# Amoled.net
KiCad netlist of a schematic drawn in Altium Designer
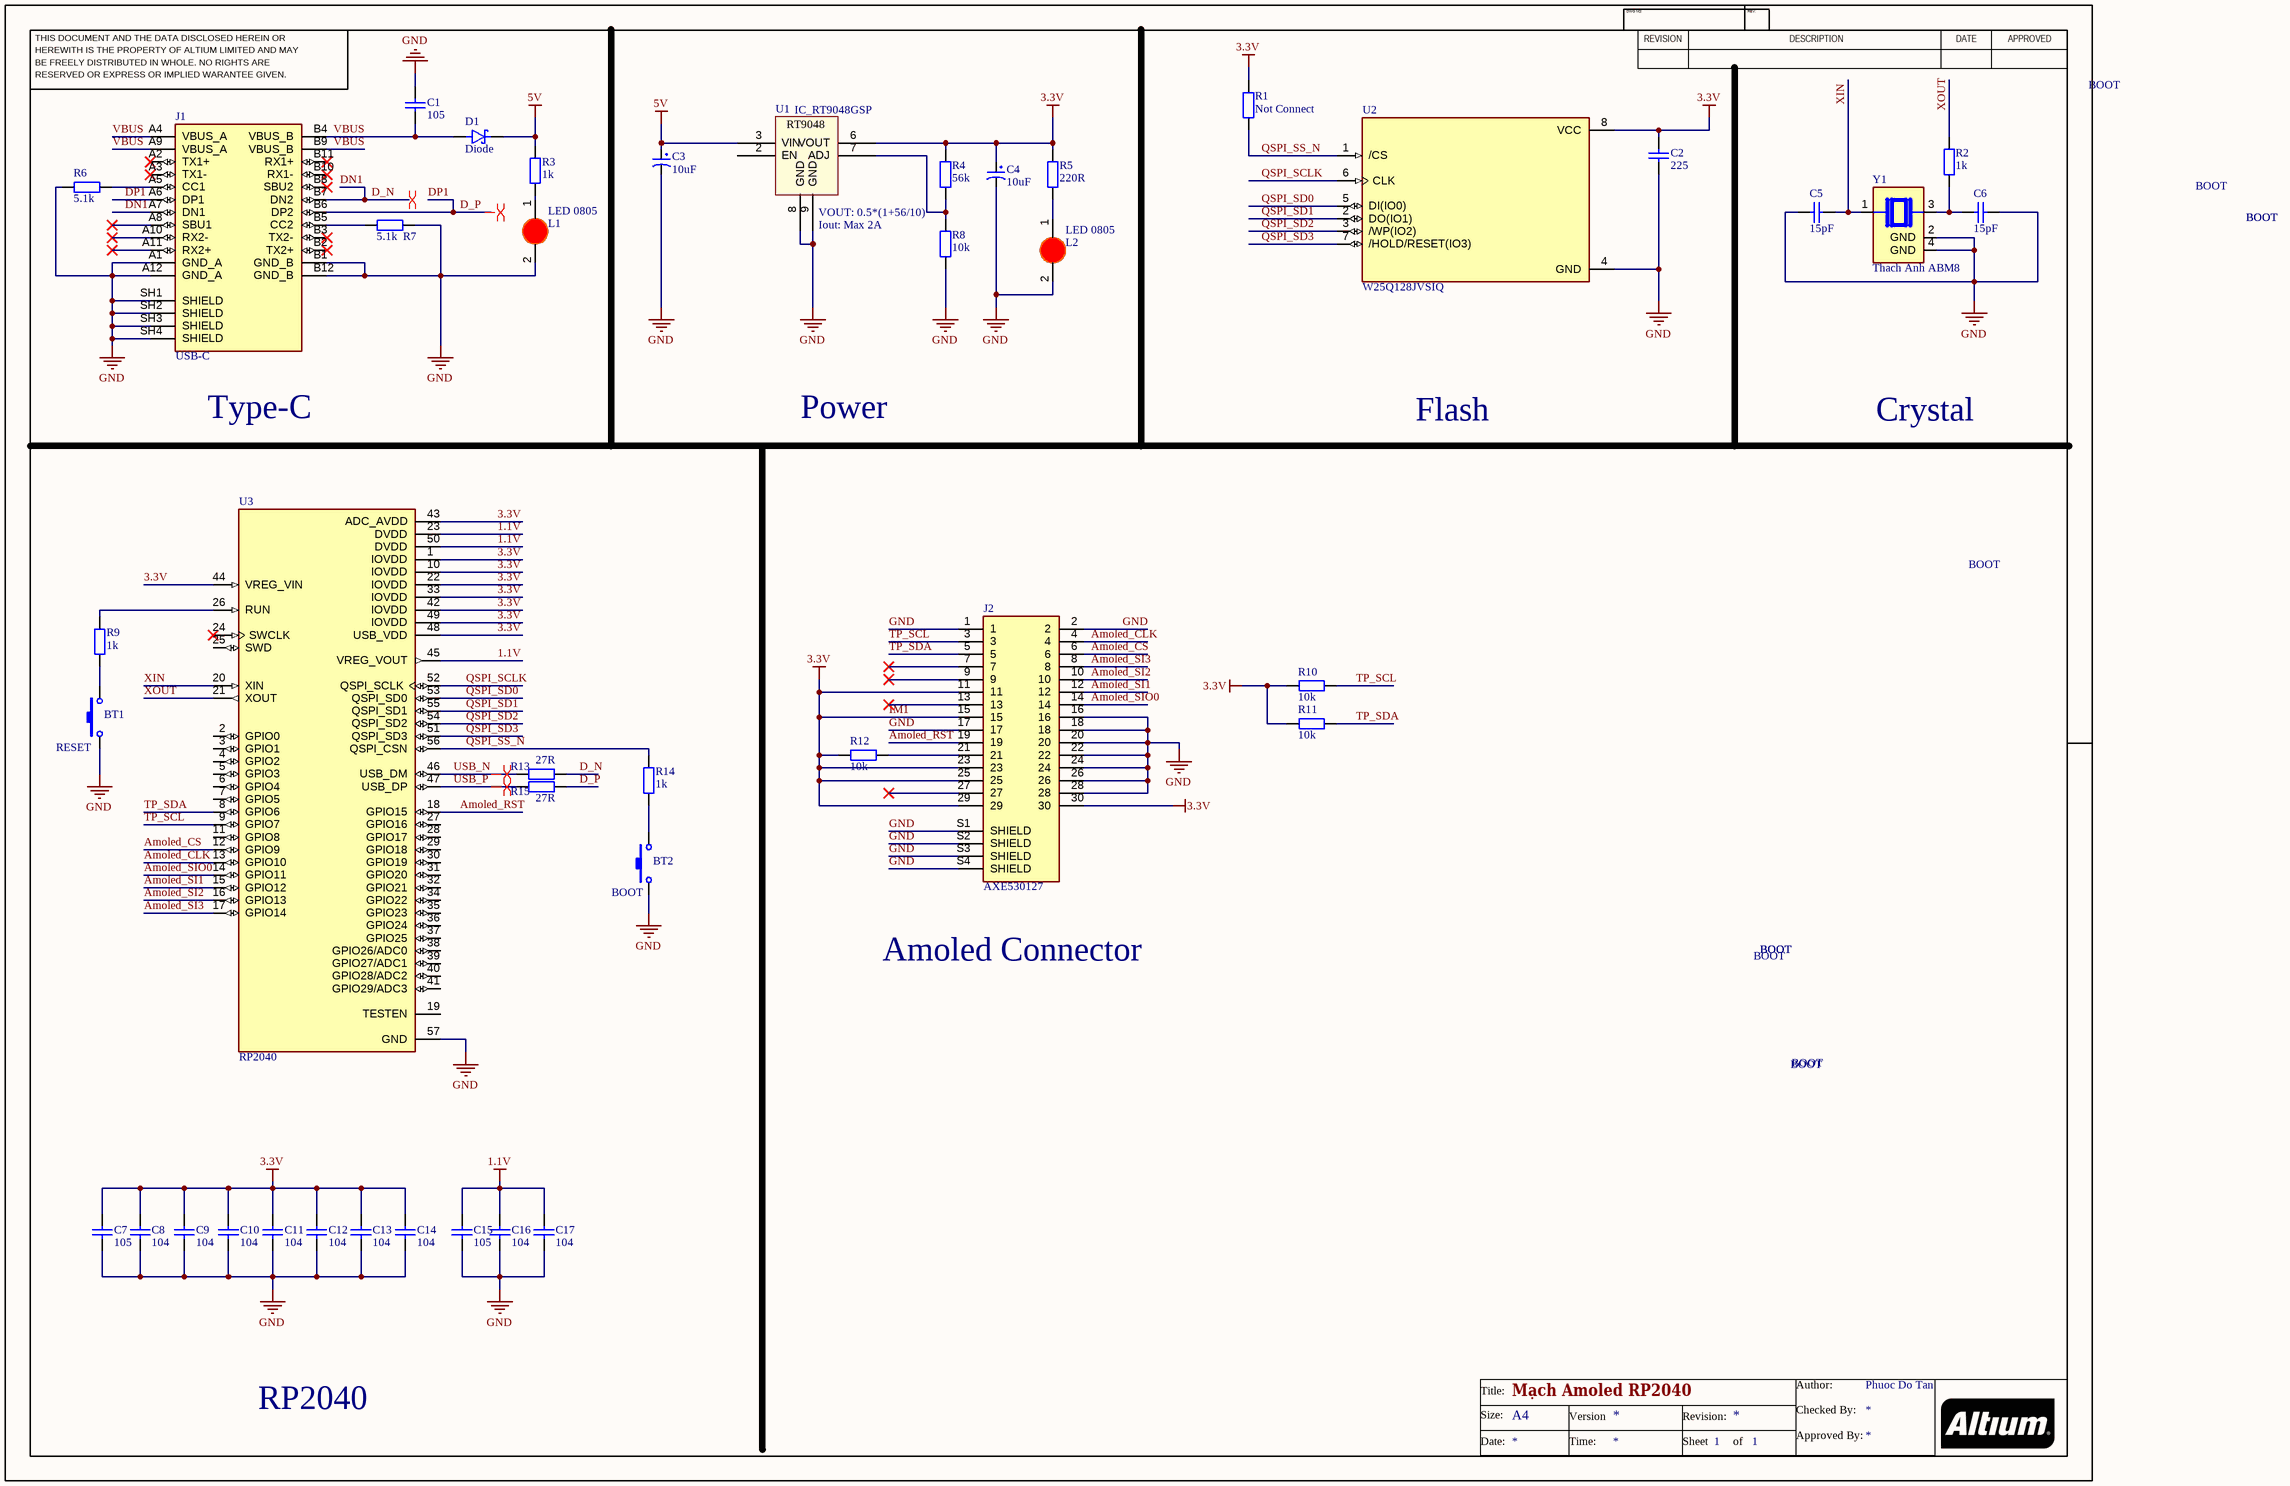
[diagram p0: Amoled.SchDoc]

(export (version "E")
  (design (tool "Eeschema 10.0.6"))
  (components
    (comp (ref "BT1")
      (value "Nut Nhan 2 Chan SMD 3x6x2.5")
      (footprint "Nut Nhan 2 Chan SMD 3x6x2.5")
      (libsource (lib "Altium_Lib_by_KhueNguyenCreator") (part "Nut Nhan 2 Chan SMD 3x6x2.5"))
    )
    (comp (ref "BT2")
      (value "Nut Nhan 2 Chan SMD 3x6x2.5")
      (footprint "Nut Nhan 2 Chan SMD 3x6x2.5")
      (libsource (lib "Altium_Lib_by_KhueNguyenCreator") (part "Nut Nhan 2 Chan SMD 3x6x2.5"))
    )
    (comp (ref "C1")
      (value "105")
      (footprint "tu 0805")
      (description "Dán")
      (libsource (lib "Altium_Lib_by_KhueNguyenCreator") (part "Tu 0805 105 50V 10%"))
    )
    (comp (ref "C2")
      (value "225")
      (footprint "tu 0805")
      (description "Dán")
      (libsource (lib "Altium_Lib_by_KhueNguyenCreator") (part "Tu 0805 225 25V 10%"))
    )
    (comp (ref "C3")
      (value "10uF")
      (footprint "tu tantalum smd3216")
      (description "Dán")
      (libsource (lib "Altium_Lib_by_KhueNguyenCreator") (part "Tu tantalum 10uF 16V SMD3216"))
    )
    (comp (ref "C4")
      (value "10uF")
      (footprint "tu tantalum smd3216")
      (description "Dán")
      (libsource (lib "Altium_Lib_by_KhueNguyenCreator") (part "Tu tantalum 10uF 16V SMD3216"))
    )
    (comp (ref "C5")
      (value "15pF")
      (footprint "tu 0805")
      (description "Dán")
      (libsource (lib "Altium_Lib_by_KhueNguyenCreator") (part "Tu 0805 15pF 50V 10%"))
    )
    (comp (ref "C6")
      (value "15pF")
      (footprint "tu 0805")
      (description "Dán")
      (libsource (lib "Altium_Lib_by_KhueNguyenCreator") (part "Tu 0805 15pF 50V 10%"))
    )
    (comp (ref "C7")
      (value "105")
      (footprint "tu 0805")
      (description "Dán")
      (libsource (lib "Altium_Lib_by_KhueNguyenCreator") (part "Tu 0805 105 50V 10%"))
    )
    (comp (ref "C8")
      (value "104")
      (footprint "tu 0805")
      (description "Dán")
      (libsource (lib "Altium_Lib_by_KhueNguyenCreator") (part "Tu 0805 104 50V 10%"))
    )
    (comp (ref "C9")
      (value "104")
      (footprint "tu 0805")
      (description "Dán")
      (libsource (lib "Altium_Lib_by_KhueNguyenCreator") (part "Tu 0805 104 50V 10%"))
    )
    (comp (ref "C10")
      (value "104")
      (footprint "tu 0805")
      (description "Dán")
      (libsource (lib "Altium_Lib_by_KhueNguyenCreator") (part "Tu 0805 104 50V 10%"))
    )
    (comp (ref "C11")
      (value "104")
      (footprint "tu 0805")
      (description "Dán")
      (libsource (lib "Altium_Lib_by_KhueNguyenCreator") (part "Tu 0805 104 50V 10%"))
    )
    (comp (ref "C12")
      (value "104")
      (footprint "tu 0805")
      (description "Dán")
      (libsource (lib "Altium_Lib_by_KhueNguyenCreator") (part "Tu 0805 104 50V 10%"))
    )
    (comp (ref "C13")
      (value "104")
      (footprint "tu 0805")
      (description "Dán")
      (libsource (lib "Altium_Lib_by_KhueNguyenCreator") (part "Tu 0805 104 50V 10%"))
    )
    (comp (ref "C14")
      (value "104")
      (footprint "tu 0805")
      (description "Dán")
      (libsource (lib "Altium_Lib_by_KhueNguyenCreator") (part "Tu 0805 104 50V 10%"))
    )
    (comp (ref "C15")
      (value "105")
      (footprint "tu 0805")
      (description "Dán")
      (libsource (lib "Altium_Lib_by_KhueNguyenCreator") (part "Tu 0805 105 50V 10%"))
    )
    (comp (ref "C16")
      (value "104")
      (footprint "tu 0805")
      (description "Dán")
      (libsource (lib "Altium_Lib_by_KhueNguyenCreator") (part "Tu 0805 104 50V 10%"))
    )
    (comp (ref "C17")
      (value "104")
      (footprint "tu 0805")
      (description "Dán")
      (libsource (lib "Altium_Lib_by_KhueNguyenCreator") (part "Tu 0805 104 50V 10%"))
    )
    (comp (ref "D1")
      (value "Diode")
      (footprint "SODFL3619X98N")
      (description "Diode Schottky 30 V 2A Surface Mount SOD-123FL")
      (fields (field (name "MF") "ON Semiconductor") (field (name "MP") "MBR230LSFT1G"))
      (libsource (lib "Altium_Lib_by_KhueNguyenCreator") (part "Diode-MBR230LSFT1G"))
    )
    (comp (ref "J1")
      (value "USB-C")
      (footprint "USB-C")
      (fields (field (name "MP") "2345986-1") (field (name "PART NUMBER") "TE2345986-1"))
      (libsource (lib "Altium_Lib_by_KhueNguyenCreator") (part "USB-C"))
    )
    (comp (ref "J2")
      (value "AXE530127")
      (footprint "PANASONIC_AXE530127")
      (description "30 Position Connector Socket, Center Strip Contacts Surface Mount Gold")
      (fields (field (name "MF") "Panasonic Electric Works"))
      (libsource (lib "Altium_Lib_by_KhueNguyenCreator") (part "AXE530127"))
    )
    (comp (ref "L1")
      (value "LED 0805")
      (footprint "LED-0805-Red")
      (description "Dán")
      (libsource (lib "Altium_Lib_by_KhueNguyenCreator") (part "LED 0805 Do"))
    )
    (comp (ref "L2")
      (value "LED 0805")
      (footprint "LED-0805-Red")
      (description "Dán")
      (libsource (lib "Altium_Lib_by_KhueNguyenCreator") (part "LED 0805 Do"))
    )
    (comp (ref "R1")
      (value "Not Connect")
      (footprint "tro smd 0805")
      (description "Dán")
      (libsource (lib "Altium_Lib_by_KhueNguyenCreator") (part "Tro 0805 5% 0R"))
    )
    (comp (ref "R2")
      (value "1k")
      (footprint "tro smd 0805")
      (description "Dán")
      (libsource (lib "Altium_Lib_by_KhueNguyenCreator") (part "Tro 0805 5% 1k"))
    )
    (comp (ref "R3")
      (value "1k")
      (footprint "tro smd 0805")
      (description "Dán")
      (libsource (lib "Altium_Lib_by_KhueNguyenCreator") (part "Tro 0805 5% 1k"))
    )
    (comp (ref "R4")
      (value "56k")
      (footprint "tro smd 0805")
      (description "Dán")
      (libsource (lib "Altium_Lib_by_KhueNguyenCreator") (part "Tro 0805 1% 510k"))
    )
    (comp (ref "R5")
      (value "220R")
      (footprint "tro smd 0805")
      (description "Dán")
      (libsource (lib "Altium_Lib_by_KhueNguyenCreator") (part "Tro 0805 5% 220R"))
    )
    (comp (ref "R6")
      (value "5.1k")
      (footprint "tro smd 0805")
      (description "Dán")
      (libsource (lib "Altium_Lib_by_KhueNguyenCreator") (part "Tro 0805 1% 5.1k"))
    )
    (comp (ref "R7")
      (value "5.1k")
      (footprint "tro smd 0805")
      (description "Dán")
      (libsource (lib "Altium_Lib_by_KhueNguyenCreator") (part "Tro 0805 1% 5.1k"))
    )
    (comp (ref "R8")
      (value "10k")
      (footprint "tro smd 0805")
      (description "Dán")
      (libsource (lib "Altium_Lib_by_KhueNguyenCreator") (part "Tro 0805 1% 10k"))
    )
    (comp (ref "R9")
      (value "1k")
      (footprint "tro smd 0805")
      (description "Dán")
      (libsource (lib "Altium_Lib_by_KhueNguyenCreator") (part "Tro 0805 5% 1k"))
    )
    (comp (ref "R10")
      (value "10k")
      (footprint "tro smd 0805")
      (description "Dán")
      (libsource (lib "Altium_Lib_by_KhueNguyenCreator") (part "Tro 0805 1% 10k"))
    )
    (comp (ref "R11")
      (value "10k")
      (footprint "tro smd 0805")
      (description "Dán")
      (libsource (lib "Altium_Lib_by_KhueNguyenCreator") (part "Tro 0805 1% 10k"))
    )
    (comp (ref "R12")
      (value "10k")
      (footprint "tro smd 0805")
      (description "Dán")
      (libsource (lib "Altium_Lib_by_KhueNguyenCreator") (part "Tro 0805 1% 10k"))
    )
    (comp (ref "R13")
      (value "27R")
      (footprint "tro smd 0805")
      (description "Dán")
      (libsource (lib "Altium_Lib_by_KhueNguyenCreator") (part "Tro 0805 1% 18k"))
    )
    (comp (ref "R14")
      (value "1k")
      (footprint "tro smd 0805")
      (description "Dán")
      (libsource (lib "Altium_Lib_by_KhueNguyenCreator") (part "Tro 0805 5% 1k"))
    )
    (comp (ref "R15")
      (value "27R")
      (footprint "tro smd 0805")
      (description "Dán")
      (libsource (lib "Altium_Lib_by_KhueNguyenCreator") (part "Tro 0805 1% 18k"))
    )
    (comp (ref "U1")
      (value "IC_RT9048GSP")
      (footprint "SOP-8(Exposed Pad)")
      (libsource (lib "Altium_Lib_by_KhueNguyenCreator") (part "IC_RT9048GSP"))
    )
    (comp (ref "U2")
      (value "W25Q128JVSIQ")
      (footprint "SOIC127P790X216-8N")
      (description "FLASH - NOR Memory IC 128Mb (16M x 8) SPI - Quad I/O, QPI, DTR 133 MHz 8-SOIC")
      (fields (field (name "MF") "Winbond Electronics"))
      (libsource (lib "Altium_Lib_by_KhueNguyenCreator") (part "W25Q128JVSIQ"))
    )
    (comp (ref "U3")
      (value "RP2040")
      (footprint "RP2040")
      (description "RP2040 chip for Raspberry Pi Pico - ARM® Cortex®-M0+ MCU 32-Bit")
      (fields (field (name "MF") "Raspberry Pi"))
      (libsource (lib "Altium_Lib_by_KhueNguyenCreator") (part "RP2040"))
    )
    (comp (ref "Y1")
      (value "Thach Anh ABM8")
      (footprint "XTAL_ABM8-272-T3")
      (description "12 MHz Â±30ppm Crystal 10pF 50 Ohms 4-SMD, No Lead")
      (fields (field (name "MF") "ABRACON") (field (name "MP") "ABM8-272-T3"))
      (libsource (lib "Altium_Lib_by_KhueNguyenCreator") (part "Thach Anh ABM8"))
    )
  )
  (nets
    (net (code "1") (name "/Amoled_CLK") (class "Default")
      (node (ref "J2") (pin "4") (pinfunction "4_4") (pintype "passive"))
      (node (ref "U3") (pin "13") (pinfunction "GPIO10_13") (pintype "bidirectional"))
    )
    (net (code "2") (name "/Amoled_CS") (class "Default")
      (node (ref "J2") (pin "6") (pinfunction "6_6") (pintype "passive"))
      (node (ref "U3") (pin "12") (pinfunction "GPIO9_12") (pintype "bidirectional"))
    )
    (net (code "3") (name "/Amoled_RST") (class "Default")
      (node (ref "J2") (pin "19") (pinfunction "19_19") (pintype "passive"))
      (node (ref "U3") (pin "18") (pinfunction "GPIO15_18") (pintype "bidirectional"))
    )
    (net (code "4") (name "/Amoled_SI1") (class "Default")
      (node (ref "J2") (pin "12") (pinfunction "12_12") (pintype "passive"))
      (node (ref "U3") (pin "15") (pinfunction "GPIO12_15") (pintype "bidirectional"))
    )
    (net (code "5") (name "/Amoled_SI2") (class "Default")
      (node (ref "J2") (pin "10") (pinfunction "10_10") (pintype "passive"))
      (node (ref "U3") (pin "16") (pinfunction "GPIO13_16") (pintype "bidirectional"))
    )
    (net (code "6") (name "/Amoled_SI3") (class "Default")
      (node (ref "J2") (pin "8") (pinfunction "8_8") (pintype "passive"))
      (node (ref "U3") (pin "17") (pinfunction "GPIO14_17") (pintype "bidirectional"))
    )
    (net (code "7") (name "/Amoled_SIO0") (class "Default")
      (node (ref "J2") (pin "14") (pinfunction "14_14") (pintype "passive"))
      (node (ref "U3") (pin "14") (pinfunction "GPIO11_14") (pintype "bidirectional"))
    )
    (net (code "8") (name "/DN1") (class "Default")
      (node (ref "J1") (pin "A7") (pinfunction "DN1_A7") (pintype "bidirectional"))
      (node (ref "J1") (pin "B7") (pinfunction "DN2_B7") (pintype "bidirectional"))
      (node (ref "R13") (pin "2") (pinfunction "2_2") (pintype "passive"))
    )
    (net (code "9") (name "/DP1") (class "Default")
      (node (ref "J1") (pin "A6") (pinfunction "DP1_A6") (pintype "bidirectional"))
      (node (ref "J1") (pin "B6") (pinfunction "DP2_B6") (pintype "bidirectional"))
      (node (ref "R15") (pin "2") (pinfunction "2_2") (pintype "passive"))
    )
    (net (code "10") (name "/QSPI_SCLK") (class "Default")
      (node (ref "U2") (pin "6") (pinfunction "CLK_6") (pintype "input"))
      (node (ref "U3") (pin "52") (pinfunction "QSPI_SCLK_52") (pintype "bidirectional"))
    )
    (net (code "11") (name "/QSPI_SD0") (class "Default")
      (node (ref "U2") (pin "5") (pinfunction "DI(IO0)_5") (pintype "bidirectional"))
      (node (ref "U3") (pin "53") (pinfunction "QSPI_SD0_53") (pintype "bidirectional"))
    )
    (net (code "12") (name "/QSPI_SD1") (class "Default")
      (node (ref "U2") (pin "2") (pinfunction "DO(IO1)_2") (pintype "bidirectional"))
      (node (ref "U3") (pin "55") (pinfunction "QSPI_SD1_55") (pintype "bidirectional"))
    )
    (net (code "13") (name "/QSPI_SD2") (class "Default")
      (node (ref "U2") (pin "3") (pinfunction "/WP(IO2)_3") (pintype "bidirectional"))
      (node (ref "U3") (pin "54") (pinfunction "QSPI_SD2_54") (pintype "bidirectional"))
    )
    (net (code "14") (name "/QSPI_SD3") (class "Default")
      (node (ref "U2") (pin "7") (pinfunction "/HOLD/RESET(IO3)_7") (pintype "bidirectional"))
      (node (ref "U3") (pin "51") (pinfunction "QSPI_SD3_51") (pintype "bidirectional"))
    )
    (net (code "15") (name "/QSPI_SS_N") (class "Default")
      (node (ref "R1") (pin "1") (pinfunction "1_1") (pintype "passive"))
      (node (ref "R14") (pin "1") (pinfunction "1_1") (pintype "passive"))
      (node (ref "U2") (pin "1") (pinfunction "/CS_1") (pintype "input"))
      (node (ref "U3") (pin "56") (pinfunction "QSPI_CSN_56") (pintype "bidirectional"))
    )
    (net (code "16") (name "/TP_SCL") (class "Default")
      (node (ref "J2") (pin "3") (pinfunction "3_3") (pintype "passive"))
      (node (ref "R10") (pin "2") (pinfunction "2_2") (pintype "passive"))
      (node (ref "U3") (pin "9") (pinfunction "GPIO7_9") (pintype "bidirectional"))
    )
    (net (code "17") (name "/TP_SDA") (class "Default")
      (node (ref "J2") (pin "5") (pinfunction "5_5") (pintype "passive"))
      (node (ref "R11") (pin "2") (pinfunction "2_2") (pintype "passive"))
      (node (ref "U3") (pin "8") (pinfunction "GPIO6_8") (pintype "bidirectional"))
    )
    (net (code "18") (name "/USB_N") (class "Default")
      (node (ref "R13") (pin "1") (pinfunction "1_1") (pintype "passive"))
      (node (ref "U3") (pin "46") (pinfunction "USB_DM_46") (pintype "bidirectional"))
    )
    (net (code "19") (name "/USB_P") (class "Default")
      (node (ref "R15") (pin "1") (pinfunction "1_1") (pintype "passive"))
      (node (ref "U3") (pin "47") (pinfunction "USB_DP_47") (pintype "bidirectional"))
    )
    (net (code "20") (name "/VBUS") (class "Default")
      (node (ref "C1") (pin "2") (pinfunction "2_2") (pintype "passive"))
      (node (ref "D1") (pin "A") (pinfunction "A_A") (pintype "passive"))
      (node (ref "J1") (pin "A4") (pinfunction "VBUS_A_A4") (pintype "power_in"))
      (node (ref "J1") (pin "A9") (pinfunction "VBUS_A_A9") (pintype "power_in"))
      (node (ref "J1") (pin "B4") (pinfunction "VBUS_B_B4") (pintype "power_in"))
      (node (ref "J1") (pin "B9") (pinfunction "VBUS_B_B9") (pintype "power_in"))
    )
    (net (code "21") (name "/XIN") (class "Default")
      (node (ref "C5") (pin "1") (pinfunction "1_1") (pintype "passive"))
      (node (ref "U3") (pin "20") (pinfunction "XIN_20") (pintype "input"))
      (node (ref "Y1") (pin "1") (pinfunction "1_1") (pintype "passive"))
    )
    (net (code "22") (name "/XOUT") (class "Default")
      (node (ref "R2") (pin "1") (pinfunction "1_1") (pintype "passive"))
      (node (ref "U3") (pin "21") (pinfunction "XOUT_21") (pintype "output"))
    )
    (net (code "23") (name "1.1V") (class "Default")
      (node (ref "C15") (pin "1") (pinfunction "1_1") (pintype "passive"))
      (node (ref "C16") (pin "1") (pinfunction "1_1") (pintype "passive"))
      (node (ref "C17") (pin "1") (pinfunction "1_1") (pintype "passive"))
      (node (ref "U3") (pin "23") (pinfunction "DVDD_23") (pintype "power_in"))
      (node (ref "U3") (pin "45") (pinfunction "VREG_VOUT_45") (pintype "output"))
      (node (ref "U3") (pin "50") (pinfunction "DVDD_50") (pintype "power_in"))
    )
    (net (code "24") (name "3.3V") (class "Default")
      (node (ref "C10") (pin "1") (pinfunction "1_1") (pintype "passive"))
      (node (ref "C11") (pin "1") (pinfunction "1_1") (pintype "passive"))
      (node (ref "C12") (pin "1") (pinfunction "1_1") (pintype "passive"))
      (node (ref "C13") (pin "1") (pinfunction "1_1") (pintype "passive"))
      (node (ref "C14") (pin "1") (pinfunction "1_1") (pintype "passive"))
      (node (ref "C2") (pin "1") (pinfunction "1_1") (pintype "passive"))
      (node (ref "C4") (pin "1") (pinfunction "1_1") (pintype "passive"))
      (node (ref "C7") (pin "1") (pinfunction "1_1") (pintype "passive"))
      (node (ref "C8") (pin "1") (pinfunction "1_1") (pintype "passive"))
      (node (ref "C9") (pin "1") (pinfunction "1_1") (pintype "passive"))
      (node (ref "J2") (pin "11") (pinfunction "11_11") (pintype "passive"))
      (node (ref "J2") (pin "15") (pinfunction "15_15") (pintype "passive"))
      (node (ref "J2") (pin "23") (pinfunction "23_23") (pintype "passive"))
      (node (ref "J2") (pin "25") (pinfunction "25_25") (pintype "passive"))
      (node (ref "J2") (pin "29") (pinfunction "29_29") (pintype "passive"))
      (node (ref "J2") (pin "30") (pinfunction "30_30") (pintype "passive"))
      (node (ref "R1") (pin "2") (pinfunction "2_2") (pintype "passive"))
      (node (ref "R10") (pin "1") (pinfunction "1_1") (pintype "passive"))
      (node (ref "R11") (pin "1") (pinfunction "1_1") (pintype "passive"))
      (node (ref "R12") (pin "1") (pinfunction "1_1") (pintype "passive"))
      (node (ref "R4") (pin "2") (pinfunction "2_2") (pintype "passive"))
      (node (ref "R5") (pin "2") (pinfunction "2_2") (pintype "passive"))
      (node (ref "U1") (pin "6") (pinfunction "VOUT_6") (pintype "passive"))
      (node (ref "U2") (pin "8") (pinfunction "VCC_8") (pintype "power_in"))
      (node (ref "U3") (pin "1") (pinfunction "IOVDD_1") (pintype "power_in"))
      (node (ref "U3") (pin "10") (pinfunction "IOVDD_10") (pintype "power_in"))
      (node (ref "U3") (pin "22") (pinfunction "IOVDD_22") (pintype "power_in"))
      (node (ref "U3") (pin "33") (pinfunction "IOVDD_33") (pintype "power_in"))
      (node (ref "U3") (pin "42") (pinfunction "IOVDD_42") (pintype "power_in"))
      (node (ref "U3") (pin "43") (pinfunction "ADC_AVDD_43") (pintype "power_in"))
      (node (ref "U3") (pin "44") (pinfunction "VREG_VIN_44") (pintype "input"))
      (node (ref "U3") (pin "48") (pinfunction "USB_VDD_48") (pintype "power_in"))
      (node (ref "U3") (pin "49") (pinfunction "IOVDD_49") (pintype "power_in"))
    )
    (net (code "25") (name "5V") (class "Default")
      (node (ref "C3") (pin "1") (pinfunction "1_1") (pintype "passive"))
      (node (ref "D1") (pin "K") (pinfunction "K_K") (pintype "passive"))
      (node (ref "R3") (pin "1") (pinfunction "1_1") (pintype "passive"))
      (node (ref "U1") (pin "3") (pinfunction "VIN_3") (pintype "passive"))
    )
    (net (code "26") (name "GND") (class "Default")
      (node (ref "BT1") (pin "1") (pinfunction "1_1") (pintype "passive"))
      (node (ref "BT2") (pin "1") (pinfunction "1_1") (pintype "passive"))
      (node (ref "C1") (pin "1") (pinfunction "1_1") (pintype "passive"))
      (node (ref "C10") (pin "2") (pinfunction "2_2") (pintype "passive"))
      (node (ref "C11") (pin "2") (pinfunction "2_2") (pintype "passive"))
      (node (ref "C12") (pin "2") (pinfunction "2_2") (pintype "passive"))
      (node (ref "C13") (pin "2") (pinfunction "2_2") (pintype "passive"))
      (node (ref "C14") (pin "2") (pinfunction "2_2") (pintype "passive"))
      (node (ref "C15") (pin "2") (pinfunction "2_2") (pintype "passive"))
      (node (ref "C16") (pin "2") (pinfunction "2_2") (pintype "passive"))
      (node (ref "C17") (pin "2") (pinfunction "2_2") (pintype "passive"))
      (node (ref "C2") (pin "2") (pinfunction "2_2") (pintype "passive"))
      (node (ref "C3") (pin "2") (pinfunction "2_2") (pintype "passive"))
      (node (ref "C4") (pin "2") (pinfunction "2_2") (pintype "passive"))
      (node (ref "C5") (pin "2") (pinfunction "2_2") (pintype "passive"))
      (node (ref "C6") (pin "1") (pinfunction "1_1") (pintype "passive"))
      (node (ref "C7") (pin "2") (pinfunction "2_2") (pintype "passive"))
      (node (ref "C8") (pin "2") (pinfunction "2_2") (pintype "passive"))
      (node (ref "C9") (pin "2") (pinfunction "2_2") (pintype "passive"))
      (node (ref "J1") (pin "A1") (pinfunction "GND_A_A1") (pintype "power_in"))
      (node (ref "J1") (pin "A12") (pinfunction "GND_A_A12") (pintype "power_in"))
      (node (ref "J1") (pin "B1") (pinfunction "GND_B_B1") (pintype "power_in"))
      (node (ref "J1") (pin "B12") (pinfunction "GND_B_B12") (pintype "power_in"))
      (node (ref "J1") (pin "SH1") (pinfunction "SHIELD_SH1") (pintype "passive"))
      (node (ref "J1") (pin "SH2") (pinfunction "SHIELD_SH2") (pintype "passive"))
      (node (ref "J1") (pin "SH3") (pinfunction "SHIELD_SH3") (pintype "passive"))
      (node (ref "J1") (pin "SH4") (pinfunction "SHIELD_SH4") (pintype "passive"))
      (node (ref "J2") (pin "1") (pinfunction "1_1") (pintype "passive"))
      (node (ref "J2") (pin "16") (pinfunction "16_16") (pintype "passive"))
      (node (ref "J2") (pin "17") (pinfunction "17_17") (pintype "passive"))
      (node (ref "J2") (pin "18") (pinfunction "18_18") (pintype "passive"))
      (node (ref "J2") (pin "2") (pinfunction "2_2") (pintype "passive"))
      (node (ref "J2") (pin "20") (pinfunction "20_20") (pintype "passive"))
      (node (ref "J2") (pin "22") (pinfunction "22_22") (pintype "passive"))
      (node (ref "J2") (pin "24") (pinfunction "24_24") (pintype "passive"))
      (node (ref "J2") (pin "26") (pinfunction "26_26") (pintype "passive"))
      (node (ref "J2") (pin "28") (pinfunction "28_28") (pintype "passive"))
      (node (ref "J2") (pin "S1") (pinfunction "SHIELD_S1") (pintype "passive"))
      (node (ref "J2") (pin "S2") (pinfunction "SHIELD_S2") (pintype "passive"))
      (node (ref "J2") (pin "S3") (pinfunction "SHIELD_S3") (pintype "passive"))
      (node (ref "J2") (pin "S4") (pinfunction "SHIELD_S4") (pintype "passive"))
      (node (ref "L1") (pin "2") (pinfunction "K_2") (pintype "passive"))
      (node (ref "L2") (pin "2") (pinfunction "K_2") (pintype "passive"))
      (node (ref "R6") (pin "1") (pinfunction "1_1") (pintype "passive"))
      (node (ref "R7") (pin "2") (pinfunction "2_2") (pintype "passive"))
      (node (ref "R8") (pin "2") (pinfunction "2_2") (pintype "passive"))
      (node (ref "U1") (pin "8") (pinfunction "GND_8") (pintype "passive"))
      (node (ref "U1") (pin "9") (pinfunction "GND_9") (pintype "passive"))
      (node (ref "U2") (pin "4") (pinfunction "GND_4") (pintype "power_in"))
      (node (ref "U3") (pin "57") (pinfunction "GND_57") (pintype "power_in"))
      (node (ref "Y1") (pin "2") (pinfunction "GND_2") (pintype "power_in"))
      (node (ref "Y1") (pin "4") (pinfunction "GND_4") (pintype "power_in"))
    )
    (net (code "27") (name "Net-(BT1-Pad2)") (class "Default")
      (node (ref "BT1") (pin "2") (pinfunction "2_2") (pintype "passive"))
      (node (ref "R9") (pin "2") (pinfunction "2_2") (pintype "passive"))
    )
    (net (code "28") (name "Net-(BT2-Pad2)") (class "Default")
      (node (ref "BT2") (pin "2") (pinfunction "2_2") (pintype "passive"))
      (node (ref "R14") (pin "2") (pinfunction "2_2") (pintype "passive"))
    )
    (net (code "29") (name "Net-(C6-Pad2)") (class "Default")
      (node (ref "C6") (pin "2") (pinfunction "2_2") (pintype "passive"))
      (node (ref "R2") (pin "2") (pinfunction "2_2") (pintype "passive"))
      (node (ref "Y1") (pin "3") (pinfunction "3_3") (pintype "passive"))
    )
    (net (code "30") (name "Net-(J1-CC1)") (class "Default")
      (node (ref "J1") (pin "A5") (pinfunction "CC1_A5") (pintype "bidirectional"))
      (node (ref "R6") (pin "2") (pinfunction "2_2") (pintype "passive"))
    )
    (net (code "31") (name "Net-(J1-CC2)") (class "Default")
      (node (ref "J1") (pin "B5") (pinfunction "CC2_B5") (pintype "bidirectional"))
      (node (ref "R7") (pin "1") (pinfunction "1_1") (pintype "passive"))
    )
    (net (code "32") (name "Net-(J2-Pad21)") (class "Default")
      (node (ref "J2") (pin "21") (pinfunction "21_21") (pintype "passive"))
      (node (ref "R12") (pin "2") (pinfunction "2_2") (pintype "passive"))
    )
    (net (code "33") (name "Net-(L1-A)") (class "Default")
      (node (ref "L1") (pin "1") (pinfunction "A_1") (pintype "passive"))
      (node (ref "R3") (pin "2") (pinfunction "2_2") (pintype "passive"))
    )
    (net (code "34") (name "Net-(L2-A)") (class "Default")
      (node (ref "L2") (pin "1") (pinfunction "A_1") (pintype "passive"))
      (node (ref "R5") (pin "1") (pinfunction "1_1") (pintype "passive"))
    )
    (net (code "35") (name "Net-(U1-ADJ)") (class "Default")
      (node (ref "R4") (pin "1") (pinfunction "1_1") (pintype "passive"))
      (node (ref "R8") (pin "1") (pinfunction "1_1") (pintype "passive"))
      (node (ref "U1") (pin "7") (pinfunction "ADJ_7") (pintype "passive"))
    )
    (net (code "36") (name "Net-(U3-RUN)") (class "Default")
      (node (ref "R9") (pin "1") (pinfunction "1_1") (pintype "passive"))
      (node (ref "U3") (pin "26") (pinfunction "RUN_26") (pintype "input"))
    )
    (net (code "37") (name "unconnected-(J1-RX1+-PadB11)") (class "Default")
      (node (ref "J1") (pin "B11") (pinfunction "RX1+_B11") (pintype "bidirectional+no_connect"))
    )
    (net (code "38") (name "unconnected-(J1-RX1--PadB10)") (class "Default")
      (node (ref "J1") (pin "B10") (pinfunction "RX1-_B10") (pintype "bidirectional+no_connect"))
    )
    (net (code "39") (name "unconnected-(J1-RX2+-PadA11)") (class "Default")
      (node (ref "J1") (pin "A11") (pinfunction "RX2+_A11") (pintype "bidirectional+no_connect"))
    )
    (net (code "40") (name "unconnected-(J1-RX2--PadA10)") (class "Default")
      (node (ref "J1") (pin "A10") (pinfunction "RX2-_A10") (pintype "bidirectional+no_connect"))
    )
    (net (code "41") (name "unconnected-(J1-SBU1-PadA8)") (class "Default")
      (node (ref "J1") (pin "A8") (pinfunction "SBU1_A8") (pintype "bidirectional+no_connect"))
    )
    (net (code "42") (name "unconnected-(J1-SBU2-PadB8)") (class "Default")
      (node (ref "J1") (pin "B8") (pinfunction "SBU2_B8") (pintype "bidirectional+no_connect"))
    )
    (net (code "43") (name "unconnected-(J1-TX1+-PadA2)") (class "Default")
      (node (ref "J1") (pin "A2") (pinfunction "TX1+_A2") (pintype "bidirectional+no_connect"))
    )
    (net (code "44") (name "unconnected-(J1-TX1--PadA3)") (class "Default")
      (node (ref "J1") (pin "A3") (pinfunction "TX1-_A3") (pintype "bidirectional+no_connect"))
    )
    (net (code "45") (name "unconnected-(J1-TX2+-PadB2)") (class "Default")
      (node (ref "J1") (pin "B2") (pinfunction "TX2+_B2") (pintype "bidirectional+no_connect"))
    )
    (net (code "46") (name "unconnected-(J1-TX2--PadB3)") (class "Default")
      (node (ref "J1") (pin "B3") (pinfunction "TX2-_B3") (pintype "bidirectional+no_connect"))
    )
    (net (code "47") (name "unconnected-(J2-Pad7)") (class "Default")
      (node (ref "J2") (pin "7") (pinfunction "7_7") (pintype "passive+no_connect"))
    )
    (net (code "48") (name "unconnected-(J2-Pad9)") (class "Default")
      (node (ref "J2") (pin "9") (pinfunction "9_9") (pintype "passive+no_connect"))
    )
    (net (code "49") (name "unconnected-(J2-Pad13)") (class "Default")
      (node (ref "J2") (pin "13") (pinfunction "13_13") (pintype "passive+no_connect"))
    )
    (net (code "50") (name "unconnected-(J2-Pad27)") (class "Default")
      (node (ref "J2") (pin "27") (pinfunction "27_27") (pintype "passive+no_connect"))
    )
    (net (code "51") (name "unconnected-(U1-EN-Pad2)") (class "Default")
      (node (ref "U1") (pin "2") (pinfunction "EN_2") (pintype "passive"))
    )
    (net (code "52") (name "unconnected-(U3-GPIO0-Pad2)") (class "Default")
      (node (ref "U3") (pin "2") (pinfunction "GPIO0_2") (pintype "bidirectional"))
    )
    (net (code "53") (name "unconnected-(U3-GPIO1-Pad3)") (class "Default")
      (node (ref "U3") (pin "3") (pinfunction "GPIO1_3") (pintype "bidirectional"))
    )
    (net (code "54") (name "unconnected-(U3-GPIO2-Pad4)") (class "Default")
      (node (ref "U3") (pin "4") (pinfunction "GPIO2_4") (pintype "bidirectional"))
    )
    (net (code "55") (name "unconnected-(U3-GPIO3-Pad5)") (class "Default")
      (node (ref "U3") (pin "5") (pinfunction "GPIO3_5") (pintype "bidirectional"))
    )
    (net (code "56") (name "unconnected-(U3-GPIO4-Pad6)") (class "Default")
      (node (ref "U3") (pin "6") (pinfunction "GPIO4_6") (pintype "bidirectional"))
    )
    (net (code "57") (name "unconnected-(U3-GPIO5-Pad7)") (class "Default")
      (node (ref "U3") (pin "7") (pinfunction "GPIO5_7") (pintype "bidirectional"))
    )
    (net (code "58") (name "unconnected-(U3-GPIO8-Pad11)") (class "Default")
      (node (ref "U3") (pin "11") (pinfunction "GPIO8_11") (pintype "bidirectional"))
    )
    (net (code "59") (name "unconnected-(U3-GPIO16-Pad27)") (class "Default")
      (node (ref "U3") (pin "27") (pinfunction "GPIO16_27") (pintype "bidirectional"))
    )
    (net (code "60") (name "unconnected-(U3-GPIO17-Pad28)") (class "Default")
      (node (ref "U3") (pin "28") (pinfunction "GPIO17_28") (pintype "bidirectional"))
    )
    (net (code "61") (name "unconnected-(U3-GPIO18-Pad29)") (class "Default")
      (node (ref "U3") (pin "29") (pinfunction "GPIO18_29") (pintype "bidirectional"))
    )
    (net (code "62") (name "unconnected-(U3-GPIO19-Pad30)") (class "Default")
      (node (ref "U3") (pin "30") (pinfunction "GPIO19_30") (pintype "bidirectional"))
    )
    (net (code "63") (name "unconnected-(U3-GPIO20-Pad31)") (class "Default")
      (node (ref "U3") (pin "31") (pinfunction "GPIO20_31") (pintype "bidirectional"))
    )
    (net (code "64") (name "unconnected-(U3-GPIO21-Pad32)") (class "Default")
      (node (ref "U3") (pin "32") (pinfunction "GPIO21_32") (pintype "bidirectional"))
    )
    (net (code "65") (name "unconnected-(U3-GPIO22-Pad34)") (class "Default")
      (node (ref "U3") (pin "34") (pinfunction "GPIO22_34") (pintype "bidirectional"))
    )
    (net (code "66") (name "unconnected-(U3-GPIO23-Pad35)") (class "Default")
      (node (ref "U3") (pin "35") (pinfunction "GPIO23_35") (pintype "bidirectional"))
    )
    (net (code "67") (name "unconnected-(U3-GPIO24-Pad36)") (class "Default")
      (node (ref "U3") (pin "36") (pinfunction "GPIO24_36") (pintype "bidirectional"))
    )
    (net (code "68") (name "unconnected-(U3-GPIO25-Pad37)") (class "Default")
      (node (ref "U3") (pin "37") (pinfunction "GPIO25_37") (pintype "bidirectional"))
    )
    (net (code "69") (name "unconnected-(U3-GPIO26{slash}ADC0-Pad38)") (class "Default")
      (node (ref "U3") (pin "38") (pinfunction "GPIO26/ADC0_38") (pintype "bidirectional"))
    )
    (net (code "70") (name "unconnected-(U3-GPIO27{slash}ADC1-Pad39)") (class "Default")
      (node (ref "U3") (pin "39") (pinfunction "GPIO27/ADC1_39") (pintype "bidirectional"))
    )
    (net (code "71") (name "unconnected-(U3-GPIO28{slash}ADC2-Pad40)") (class "Default")
      (node (ref "U3") (pin "40") (pinfunction "GPIO28/ADC2_40") (pintype "bidirectional"))
    )
    (net (code "72") (name "unconnected-(U3-GPIO29{slash}ADC3-Pad41)") (class "Default")
      (node (ref "U3") (pin "41") (pinfunction "GPIO29/ADC3_41") (pintype "bidirectional"))
    )
    (net (code "73") (name "unconnected-(U3-SWCLK-Pad24)") (class "Default")
      (node (ref "U3") (pin "24") (pinfunction "SWCLK_24") (pintype "input+no_connect"))
    )
    (net (code "74") (name "unconnected-(U3-SWD-Pad25)") (class "Default")
      (node (ref "U3") (pin "25") (pinfunction "SWD_25") (pintype "bidirectional"))
    )
    (net (code "75") (name "unconnected-(U3-TESTEN-Pad19)") (class "Default")
      (node (ref "U3") (pin "19") (pinfunction "TESTEN_19") (pintype "passive"))
    )
  )
)
